# RiadenieMotorovL293D.net
KiCad netlist of a schematic drawn in EAGLE
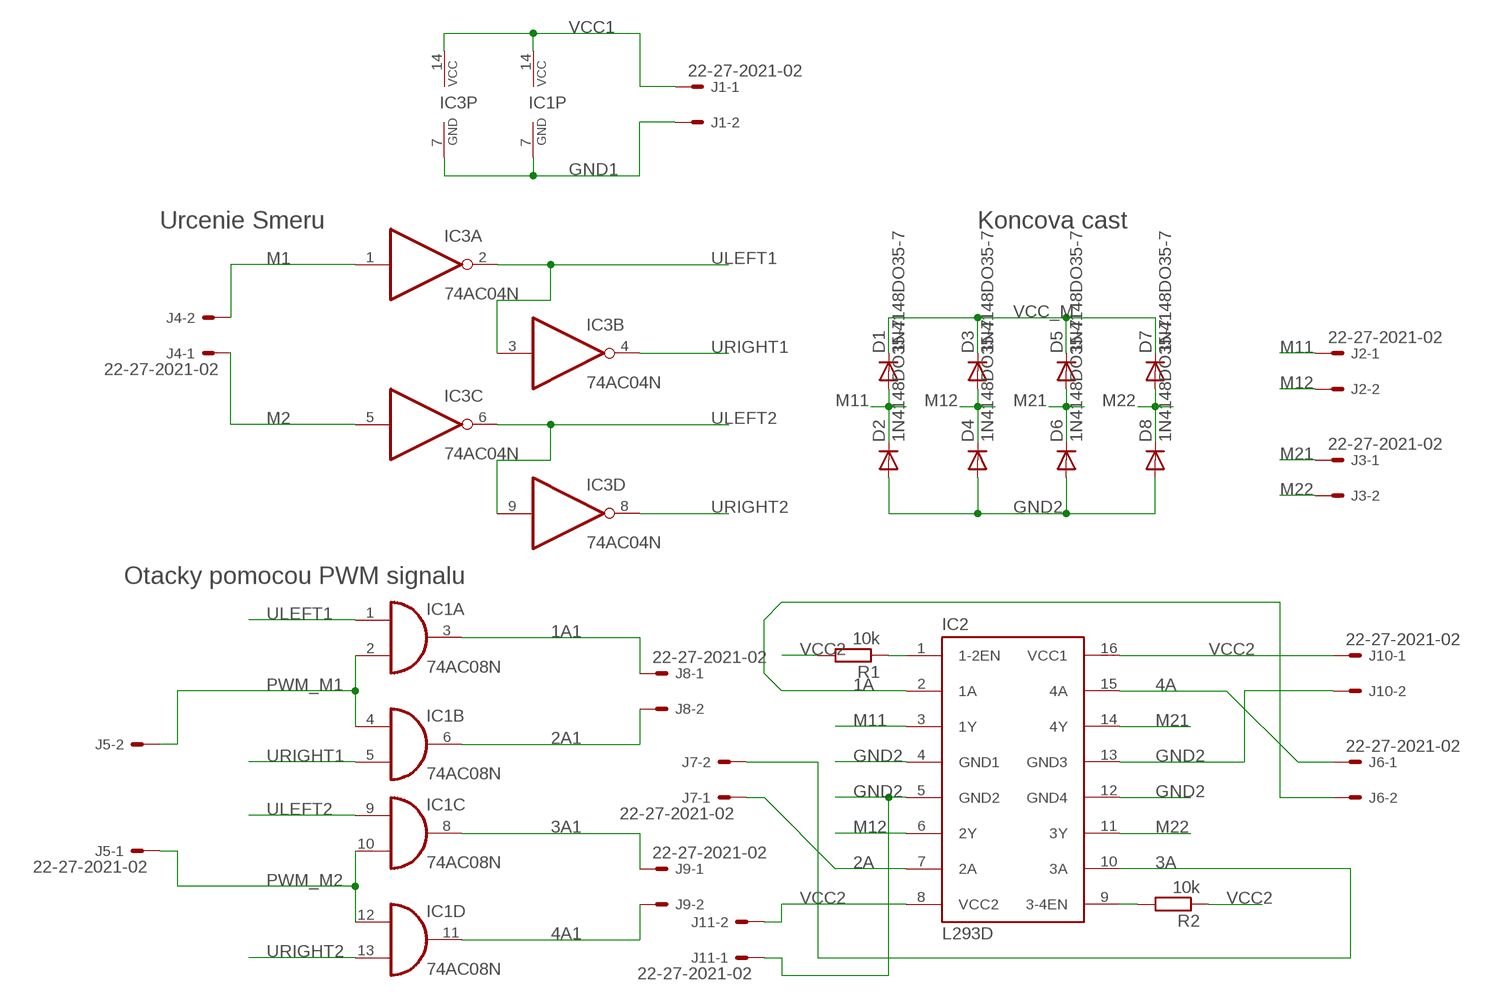
[diagram p0: schematic, sheet 1]

(export (version "E")
  (design (tool "Eeschema 10.0.6"))
  (components
    (comp (ref "D1")
      (value "1N4148DO35-7")
      (footprint "eagle-import:DO35-7")
      (libsource (lib "eagle-import") (part "1N4148DO35-7"))
    )
    (comp (ref "D2")
      (value "1N4148DO35-7")
      (footprint "eagle-import:DO35-7")
      (libsource (lib "eagle-import") (part "1N4148DO35-7"))
    )
    (comp (ref "D3")
      (value "1N4148DO35-7")
      (footprint "eagle-import:DO35-7")
      (libsource (lib "eagle-import") (part "1N4148DO35-7"))
    )
    (comp (ref "D4")
      (value "1N4148DO35-7")
      (footprint "eagle-import:DO35-7")
      (libsource (lib "eagle-import") (part "1N4148DO35-7"))
    )
    (comp (ref "D5")
      (value "1N4148DO35-7")
      (footprint "eagle-import:DO35-7")
      (libsource (lib "eagle-import") (part "1N4148DO35-7"))
    )
    (comp (ref "D6")
      (value "1N4148DO35-7")
      (footprint "eagle-import:DO35-7")
      (libsource (lib "eagle-import") (part "1N4148DO35-7"))
    )
    (comp (ref "D7")
      (value "1N4148DO35-7")
      (footprint "eagle-import:DO35-7")
      (libsource (lib "eagle-import") (part "1N4148DO35-7"))
    )
    (comp (ref "D8")
      (value "1N4148DO35-7")
      (footprint "eagle-import:DO35-7")
      (libsource (lib "eagle-import") (part "1N4148DO35-7"))
    )
    (comp (ref "IC1")
      (value "74AC08N")
      (footprint "eagle-import:DIL14")
      (libsource (lib "eagle-import") (part "7408NAC"))
    )
    (comp (ref "IC2")
      (value "L293D")
      (footprint "eagle-import:DIL16")
      (libsource (lib "eagle-import") (part "L293D"))
    )
    (comp (ref "IC3")
      (value "74AC04N")
      (footprint "eagle-import:DIL14")
      (libsource (lib "eagle-import") (part "7404NAC"))
    )
    (comp (ref "J1")
      (value "22-27-2021-02")
      (footprint "eagle-import:6410-02")
      (libsource (lib "eagle-import") (part "22-?-0227-2021"))
    )
    (comp (ref "J2")
      (value "22-27-2021-02")
      (footprint "eagle-import:6410-02")
      (libsource (lib "eagle-import") (part "22-?-0227-2021"))
    )
    (comp (ref "J3")
      (value "22-27-2021-02")
      (footprint "eagle-import:6410-02")
      (libsource (lib "eagle-import") (part "22-?-0227-2021"))
    )
    (comp (ref "J4")
      (value "22-27-2021-02")
      (footprint "eagle-import:6410-02")
      (libsource (lib "eagle-import") (part "22-?-0227-2021"))
    )
    (comp (ref "J5")
      (value "22-27-2021-02")
      (footprint "eagle-import:6410-02")
      (libsource (lib "eagle-import") (part "22-?-0227-2021"))
    )
    (comp (ref "J6")
      (value "22-27-2021-02")
      (footprint "eagle-import:6410-02")
      (libsource (lib "eagle-import") (part "22-?-0227-2021"))
    )
    (comp (ref "J7")
      (value "22-27-2021-02")
      (footprint "eagle-import:6410-02")
      (libsource (lib "eagle-import") (part "22-?-0227-2021"))
    )
    (comp (ref "J8")
      (value "22-27-2021-02")
      (footprint "eagle-import:6410-02")
      (libsource (lib "eagle-import") (part "22-?-0227-2021"))
    )
    (comp (ref "J9")
      (value "22-27-2021-02")
      (footprint "eagle-import:6410-02")
      (libsource (lib "eagle-import") (part "22-?-0227-2021"))
    )
    (comp (ref "J10")
      (value "22-27-2021-02")
      (footprint "eagle-import:6410-02")
      (libsource (lib "eagle-import") (part "22-?-0227-2021"))
    )
    (comp (ref "J11")
      (value "22-27-2021-02")
      (footprint "eagle-import:6410-02")
      (libsource (lib "eagle-import") (part "22-?-0227-2021"))
    )
    (comp (ref "R1")
      (value "10k")
      (footprint "eagle-import:0207_10")
      (libsource (lib "eagle-import") (part "R-EU_0207/10"))
    )
    (comp (ref "R2")
      (value "10k")
      (footprint "eagle-import:0207_10")
      (libsource (lib "eagle-import") (part "R-EU_0207/10"))
    )
  )
  (nets
    (net (code "1") (name "/1A") (class "Default")
      (node (ref "IC2") (pin "2") (pinfunction "1A_2") (pintype "input"))
      (node (ref "J6") (pin "2") (pinfunction "S_2") (pintype "passive"))
    )
    (net (code "2") (name "/1A1") (class "Default")
      (node (ref "IC1") (pin "3") (pinfunction "O_3") (pintype "output"))
      (node (ref "J8") (pin "1") (pinfunction "S_1") (pintype "passive"))
    )
    (net (code "3") (name "/2A") (class "Default")
      (node (ref "IC2") (pin "7") (pinfunction "2A_7") (pintype "input"))
      (node (ref "J7") (pin "1") (pinfunction "S_1") (pintype "passive"))
    )
    (net (code "4") (name "/2A1") (class "Default")
      (node (ref "IC1") (pin "6") (pinfunction "O_6") (pintype "output"))
      (node (ref "J8") (pin "2") (pinfunction "S_2") (pintype "passive"))
    )
    (net (code "5") (name "/3A") (class "Default")
      (node (ref "IC2") (pin "10") (pinfunction "3A_10") (pintype "input"))
      (node (ref "J7") (pin "2") (pinfunction "S_2") (pintype "passive"))
    )
    (net (code "6") (name "/3A1") (class "Default")
      (node (ref "IC1") (pin "8") (pinfunction "O_8") (pintype "output"))
      (node (ref "J9") (pin "1") (pinfunction "S_1") (pintype "passive"))
    )
    (net (code "7") (name "/4A") (class "Default")
      (node (ref "IC2") (pin "15") (pinfunction "4A_15") (pintype "input"))
      (node (ref "J6") (pin "1") (pinfunction "S_1") (pintype "passive"))
    )
    (net (code "8") (name "/4A1") (class "Default")
      (node (ref "IC1") (pin "11") (pinfunction "O_11") (pintype "output"))
      (node (ref "J9") (pin "2") (pinfunction "S_2") (pintype "passive"))
    )
    (net (code "9") (name "/GND1") (class "Default")
      (node (ref "IC1") (pin "7") (pinfunction "GND_7") (pintype "power_in"))
      (node (ref "IC3") (pin "7") (pinfunction "GND_7") (pintype "power_in"))
      (node (ref "J1") (pin "2") (pinfunction "S_2") (pintype "passive"))
    )
    (net (code "10") (name "/GND2") (class "Default")
      (node (ref "D2") (pin "A") (pinfunction "A_A") (pintype "passive"))
      (node (ref "D4") (pin "A") (pinfunction "A_A") (pintype "passive"))
      (node (ref "D6") (pin "A") (pinfunction "A_A") (pintype "passive"))
      (node (ref "D8") (pin "A") (pinfunction "A_A") (pintype "passive"))
      (node (ref "IC2") (pin "12") (pinfunction "GND4_12") (pintype "power_in"))
      (node (ref "IC2") (pin "13") (pinfunction "GND3_13") (pintype "power_in"))
      (node (ref "IC2") (pin "4") (pinfunction "GND1_4") (pintype "power_in"))
      (node (ref "IC2") (pin "5") (pinfunction "GND2_5") (pintype "power_in"))
      (node (ref "J10") (pin "2") (pinfunction "S_2") (pintype "passive"))
      (node (ref "J11") (pin "1") (pinfunction "S_1") (pintype "passive"))
    )
    (net (code "11") (name "/M1") (class "Default")
      (node (ref "IC3") (pin "1") (pinfunction "I_1") (pintype "input"))
      (node (ref "J4") (pin "2") (pinfunction "S_2") (pintype "passive"))
    )
    (net (code "12") (name "/M2") (class "Default")
      (node (ref "IC3") (pin "5") (pinfunction "I_5") (pintype "input"))
      (node (ref "J4") (pin "1") (pinfunction "S_1") (pintype "passive"))
    )
    (net (code "13") (name "/M11") (class "Default")
      (node (ref "D1") (pin "A") (pinfunction "A_A") (pintype "passive"))
      (node (ref "D2") (pin "C") (pinfunction "C_C") (pintype "passive"))
      (node (ref "IC2") (pin "3") (pinfunction "1Y_3") (pintype "output"))
      (node (ref "J2") (pin "1") (pinfunction "S_1") (pintype "passive"))
    )
    (net (code "14") (name "/M12") (class "Default")
      (node (ref "D3") (pin "A") (pinfunction "A_A") (pintype "passive"))
      (node (ref "D4") (pin "C") (pinfunction "C_C") (pintype "passive"))
      (node (ref "IC2") (pin "6") (pinfunction "2Y_6") (pintype "output"))
      (node (ref "J2") (pin "2") (pinfunction "S_2") (pintype "passive"))
    )
    (net (code "15") (name "/M21") (class "Default")
      (node (ref "D5") (pin "A") (pinfunction "A_A") (pintype "passive"))
      (node (ref "D6") (pin "C") (pinfunction "C_C") (pintype "passive"))
      (node (ref "IC2") (pin "14") (pinfunction "4Y_14") (pintype "output"))
      (node (ref "J3") (pin "1") (pinfunction "S_1") (pintype "passive"))
    )
    (net (code "16") (name "/M22") (class "Default")
      (node (ref "D7") (pin "A") (pinfunction "A_A") (pintype "passive"))
      (node (ref "D8") (pin "C") (pinfunction "C_C") (pintype "passive"))
      (node (ref "IC2") (pin "11") (pinfunction "3Y_11") (pintype "output"))
      (node (ref "J3") (pin "2") (pinfunction "S_2") (pintype "passive"))
    )
    (net (code "17") (name "/PWM_M1") (class "Default")
      (node (ref "IC1") (pin "2") (pinfunction "I1_2") (pintype "input"))
      (node (ref "IC1") (pin "4") (pinfunction "I0_4") (pintype "input"))
      (node (ref "J5") (pin "2") (pinfunction "S_2") (pintype "passive"))
    )
    (net (code "18") (name "/PWM_M2") (class "Default")
      (node (ref "IC1") (pin "10") (pinfunction "I1_10") (pintype "input"))
      (node (ref "IC1") (pin "12") (pinfunction "I0_12") (pintype "input"))
      (node (ref "J5") (pin "1") (pinfunction "S_1") (pintype "passive"))
    )
    (net (code "19") (name "/ULEFT1") (class "Default")
      (node (ref "IC1") (pin "1") (pinfunction "I0_1") (pintype "input"))
      (node (ref "IC3") (pin "2") (pinfunction "O_2") (pintype "output"))
      (node (ref "IC3") (pin "3") (pinfunction "I_3") (pintype "input"))
    )
    (net (code "20") (name "/ULEFT2") (class "Default")
      (node (ref "IC1") (pin "9") (pinfunction "I0_9") (pintype "input"))
      (node (ref "IC3") (pin "6") (pinfunction "O_6") (pintype "output"))
      (node (ref "IC3") (pin "9") (pinfunction "I_9") (pintype "input"))
    )
    (net (code "21") (name "/URIGHT1") (class "Default")
      (node (ref "IC1") (pin "5") (pinfunction "I1_5") (pintype "input"))
      (node (ref "IC3") (pin "4") (pinfunction "O_4") (pintype "output"))
    )
    (net (code "22") (name "/URIGHT2") (class "Default")
      (node (ref "IC1") (pin "13") (pinfunction "I1_13") (pintype "input"))
      (node (ref "IC3") (pin "8") (pinfunction "O_8") (pintype "output"))
    )
    (net (code "23") (name "/VCC1") (class "Default")
      (node (ref "IC1") (pin "14") (pinfunction "VCC_14") (pintype "power_in"))
      (node (ref "IC3") (pin "14") (pinfunction "VCC_14") (pintype "power_in"))
      (node (ref "J1") (pin "1") (pinfunction "S_1") (pintype "passive"))
    )
    (net (code "24") (name "/VCC2") (class "Default")
      (node (ref "IC2") (pin "16") (pinfunction "VCC1_16") (pintype "power_in"))
      (node (ref "IC2") (pin "8") (pinfunction "VCC2_8") (pintype "power_in"))
      (node (ref "J10") (pin "1") (pinfunction "S_1") (pintype "passive"))
      (node (ref "J11") (pin "2") (pinfunction "S_2") (pintype "passive"))
      (node (ref "R1") (pin "2") (pinfunction "2_2") (pintype "passive"))
      (node (ref "R2") (pin "1") (pinfunction "1_1") (pintype "passive"))
    )
    (net (code "25") (name "/VCC_M") (class "Default")
      (node (ref "D1") (pin "C") (pinfunction "C_C") (pintype "passive"))
      (node (ref "D3") (pin "C") (pinfunction "C_C") (pintype "passive"))
      (node (ref "D5") (pin "C") (pinfunction "C_C") (pintype "passive"))
      (node (ref "D7") (pin "C") (pinfunction "C_C") (pintype "passive"))
    )
    (net (code "26") (name "Net-(IC2-1-2EN)") (class "Default")
      (node (ref "IC2") (pin "1") (pinfunction "1-2EN_1") (pintype "input"))
      (node (ref "R1") (pin "1") (pinfunction "1_1") (pintype "passive"))
    )
    (net (code "27") (name "Net-(IC2-3-4EN)") (class "Default")
      (node (ref "IC2") (pin "9") (pinfunction "3-4EN_9") (pintype "input"))
      (node (ref "R2") (pin "2") (pinfunction "2_2") (pintype "passive"))
    )
  )
)
